# espurna-h.net
KiCad netlist of a schematic drawn in EAGLE
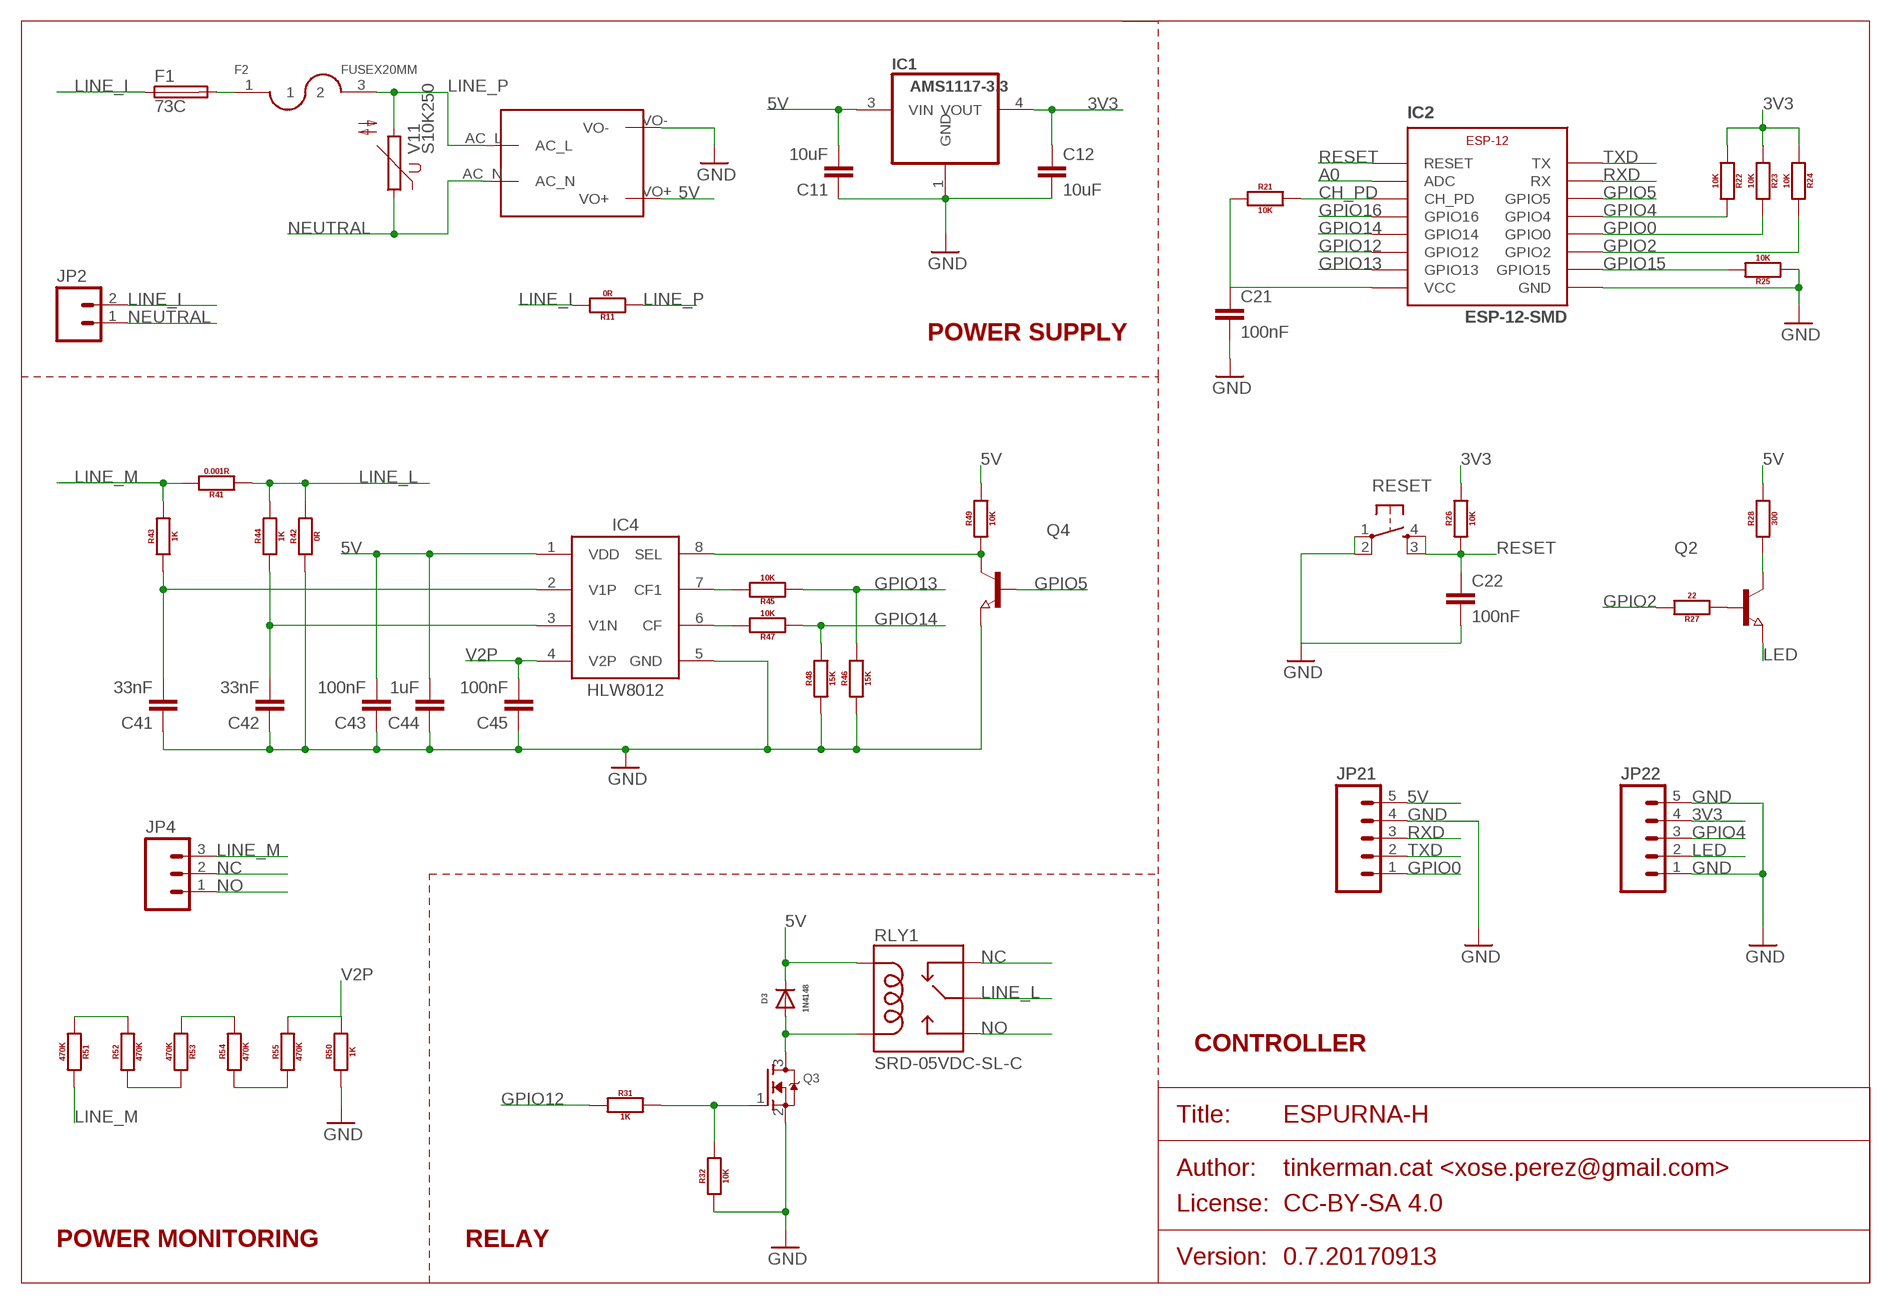
[diagram p0: schematic, sheet 1]

(export (version "E")
  (design (tool "Eeschema 10.0.6"))
  (components
    (comp (ref "C11")
      (value "10uF")
      (footprint "eagle-import:0805")
      (libsource (lib "eagle-import") (part "C-EU0805"))
    )
    (comp (ref "C12")
      (value "10uF")
      (footprint "eagle-import:0805")
      (libsource (lib "eagle-import") (part "C-EU0805"))
    )
    (comp (ref "C21")
      (value "100nF")
      (footprint "eagle-import:0805")
      (libsource (lib "eagle-import") (part "C-EU0805"))
    )
    (comp (ref "C22")
      (value "100nF")
      (footprint "eagle-import:0805")
      (libsource (lib "eagle-import") (part "C-EU0805"))
    )
    (comp (ref "C41")
      (value "33nF")
      (footprint "eagle-import:0805")
      (libsource (lib "eagle-import") (part "C-EU0805"))
    )
    (comp (ref "C42")
      (value "33nF")
      (footprint "eagle-import:0805")
      (libsource (lib "eagle-import") (part "C-EU0805"))
    )
    (comp (ref "C43")
      (value "100nF")
      (footprint "eagle-import:0805")
      (libsource (lib "eagle-import") (part "C-EU0805"))
    )
    (comp (ref "C44")
      (value "1uF")
      (footprint "eagle-import:0805")
      (libsource (lib "eagle-import") (part "C-EU0805"))
    )
    (comp (ref "C45")
      (value "100nF")
      (footprint "eagle-import:0805")
      (libsource (lib "eagle-import") (part "C-EU0805"))
    )
    (comp (ref "D3")
      (value "1N4148")
      (footprint "eagle-import:SOD80")
      (libsource (lib "eagle-import") (part "DIODE"))
    )
    (comp (ref "F1")
      (value "73C")
      (footprint "eagle-import:PICOFUSE")
      (libsource (lib "eagle-import") (part "PICOFUSE"))
    )
    (comp (ref "F2")
      (value "FUSEX20MM")
      (footprint "eagle-import:FUSE_5MM")
      (libsource (lib "eagle-import") (part "FUSEX20MM"))
    )
    (comp (ref "IC1")
      (value "AMS1117-3.3")
      (footprint "eagle-import:SOT223")
      (libsource (lib "eagle-import") (part "REG1117SOT223-2"))
    )
    (comp (ref "IC2")
      (value "ESP-12-SMD")
      (footprint "eagle-import:ESP-12-SMD")
      (libsource (lib "eagle-import") (part "ESP-12-SMD"))
    )
    (comp (ref "IC4")
      (value "HLW8012")
      (footprint "eagle-import:SOP8")
      (libsource (lib "eagle-import") (part "HLW8012"))
    )
    (comp (ref "JP2")
      (value "M02200MIL")
      (footprint "eagle-import:SCREWTERMINAL-200MIL-2")
      (libsource (lib "eagle-import") (part "M02200MIL"))
    )
    (comp (ref "JP4")
      (value "M03200MIL")
      (footprint "eagle-import:SCREWTERMINAL-200MIL-3")
      (libsource (lib "eagle-import") (part "M03200MIL"))
    )
    (comp (ref "JP21")
      (value "M05PTH")
      (footprint "eagle-import:1X05")
      (libsource (lib "eagle-import") (part "M05PTH"))
    )
    (comp (ref "JP22")
      (value "M05PTH")
      (footprint "eagle-import:1X05")
      (libsource (lib "eagle-import") (part "M05PTH"))
    )
    (comp (ref "Q2")
      (value "NPN-TRANSISTOR_SOT23")
      (footprint "eagle-import:SOT23")
      (libsource (lib "eagle-import") (part "NPN-TRANSISTOR_SOT23"))
    )
    (comp (ref "Q3")
      (value "MOSFET-NREFLOW")
      (footprint "eagle-import:SOT23")
      (libsource (lib "eagle-import") (part "MOSFET-NREFLOW"))
    )
    (comp (ref "Q4")
      (value "NPN-TRANSISTOR_SOT23")
      (footprint "eagle-import:SOT23")
      (libsource (lib "eagle-import") (part "NPN-TRANSISTOR_SOT23"))
    )
    (comp (ref "R11")
      (value "0R")
      (footprint "eagle-import:1206")
      (libsource (lib "eagle-import") (part "RESISTOR1206"))
    )
    (comp (ref "R21")
      (value "10K")
      (footprint "eagle-import:0805")
      (libsource (lib "eagle-import") (part "RESISTOR0805"))
    )
    (comp (ref "R22")
      (value "10K")
      (footprint "eagle-import:0805")
      (libsource (lib "eagle-import") (part "RESISTOR0805"))
    )
    (comp (ref "R23")
      (value "10K")
      (footprint "eagle-import:0805")
      (libsource (lib "eagle-import") (part "RESISTOR0805"))
    )
    (comp (ref "R24")
      (value "10K")
      (footprint "eagle-import:0805")
      (libsource (lib "eagle-import") (part "RESISTOR0805"))
    )
    (comp (ref "R25")
      (value "10K")
      (footprint "eagle-import:0805")
      (libsource (lib "eagle-import") (part "RESISTOR0805"))
    )
    (comp (ref "R26")
      (value "10K")
      (footprint "eagle-import:0805")
      (libsource (lib "eagle-import") (part "RESISTOR0805"))
    )
    (comp (ref "R27")
      (value "22")
      (footprint "eagle-import:0805")
      (libsource (lib "eagle-import") (part "RESISTOR0805"))
    )
    (comp (ref "R28")
      (value "300")
      (footprint "eagle-import:0805")
      (libsource (lib "eagle-import") (part "RESISTOR0805"))
    )
    (comp (ref "R31")
      (value "1K")
      (footprint "eagle-import:0805")
      (libsource (lib "eagle-import") (part "RESISTOR0805"))
    )
    (comp (ref "R32")
      (value "10K")
      (footprint "eagle-import:0805")
      (libsource (lib "eagle-import") (part "RESISTOR0805"))
    )
    (comp (ref "R41")
      (value "0.001R")
      (footprint "eagle-import:2512")
      (libsource (lib "eagle-import") (part "RESISTOR2512"))
    )
    (comp (ref "R42")
      (value "0R")
      (footprint "eagle-import:1206")
      (libsource (lib "eagle-import") (part "RESISTOR1206"))
    )
    (comp (ref "R43")
      (value "1K")
      (footprint "eagle-import:0805")
      (libsource (lib "eagle-import") (part "RESISTOR0805"))
    )
    (comp (ref "R44")
      (value "1K")
      (footprint "eagle-import:0805")
      (libsource (lib "eagle-import") (part "RESISTOR0805"))
    )
    (comp (ref "R45")
      (value "10K")
      (footprint "eagle-import:0805")
      (libsource (lib "eagle-import") (part "RESISTOR0805"))
    )
    (comp (ref "R46")
      (value "15K")
      (footprint "eagle-import:0805")
      (libsource (lib "eagle-import") (part "RESISTOR0805"))
    )
    (comp (ref "R47")
      (value "10K")
      (footprint "eagle-import:0805")
      (libsource (lib "eagle-import") (part "RESISTOR0805"))
    )
    (comp (ref "R48")
      (value "15K")
      (footprint "eagle-import:0805")
      (libsource (lib "eagle-import") (part "RESISTOR0805"))
    )
    (comp (ref "R49")
      (value "10K")
      (footprint "eagle-import:0805")
      (libsource (lib "eagle-import") (part "RESISTOR0805"))
    )
    (comp (ref "R50")
      (value "1K")
      (footprint "eagle-import:0805")
      (libsource (lib "eagle-import") (part "RESISTOR0805"))
    )
    (comp (ref "R51")
      (value "470K")
      (footprint "eagle-import:0805")
      (libsource (lib "eagle-import") (part "RESISTOR0805"))
    )
    (comp (ref "R52")
      (value "470K")
      (footprint "eagle-import:0805")
      (libsource (lib "eagle-import") (part "RESISTOR0805"))
    )
    (comp (ref "R53")
      (value "470K")
      (footprint "eagle-import:0805")
      (libsource (lib "eagle-import") (part "RESISTOR0805"))
    )
    (comp (ref "R54")
      (value "470K")
      (footprint "eagle-import:0805")
      (libsource (lib "eagle-import") (part "RESISTOR0805"))
    )
    (comp (ref "R55")
      (value "470K")
      (footprint "eagle-import:0805")
      (libsource (lib "eagle-import") (part "RESISTOR0805"))
    )
    (comp (ref "RESET")
      (value "TACTILE_BUTTON_SMD")
      (footprint "eagle-import:TACTILE-BUTTON-SMD")
      (libsource (lib "eagle-import") (part "TACTILE_BUTTON_SMD"))
    )
    (comp (ref "RLY1")
      (value "SRD-05VDC-SL-C")
      (footprint "eagle-import:SRD-5VDC-SL-C")
      (libsource (lib "eagle-import") (part "RELAYSONGLE"))
    )
    (comp (ref "U$1")
      (value "MAINS_CONVERTERS")
      (footprint "eagle-import:HLK-PM01")
      (libsource (lib "eagle-import") (part "MAINS_CONVERTERS"))
    )
    (comp (ref "V11")
      (value "S10K250")
      (footprint "eagle-import:S10K250")
      (libsource (lib "eagle-import") (part "S10K250"))
    )
  )
  (nets
    (net (code "1") (name "/3V3") (class "Default")
      (node (ref "C12") (pin "1") (pinfunction "1_1") (pintype "passive"))
      (node (ref "C21") (pin "1") (pinfunction "1_1") (pintype "passive"))
      (node (ref "IC1") (pin "4") (pinfunction "VOUT_4") (pintype "output"))
      (node (ref "IC2") (pin "VCC") (pinfunction "VCC_VCC") (pintype "bidirectional"))
      (node (ref "JP22") (pin "4") (pinfunction "4_4") (pintype "passive"))
      (node (ref "R21") (pin "1") (pinfunction "1_1") (pintype "passive"))
      (node (ref "R22") (pin "1") (pinfunction "1_1") (pintype "passive"))
      (node (ref "R23") (pin "1") (pinfunction "1_1") (pintype "passive"))
      (node (ref "R24") (pin "1") (pinfunction "1_1") (pintype "passive"))
      (node (ref "R26") (pin "2") (pinfunction "2_2") (pintype "passive"))
    )
    (net (code "2") (name "/5V") (class "Default")
      (node (ref "C11") (pin "2") (pinfunction "2_2") (pintype "passive"))
      (node (ref "C43") (pin "2") (pinfunction "2_2") (pintype "passive"))
      (node (ref "C44") (pin "2") (pinfunction "2_2") (pintype "passive"))
      (node (ref "D3") (pin "2") (pinfunction "C_2") (pintype "passive"))
      (node (ref "IC1") (pin "3") (pinfunction "VIN_3") (pintype "input"))
      (node (ref "IC4") (pin "1") (pinfunction "VDD_1") (pintype "power_in"))
      (node (ref "JP21") (pin "5") (pinfunction "5_5") (pintype "passive"))
      (node (ref "R28") (pin "2") (pinfunction "2_2") (pintype "passive"))
      (node (ref "R49") (pin "2") (pinfunction "2_2") (pintype "passive"))
      (node (ref "RLY1") (pin "COIL1") (pinfunction "COIL1_COIL1") (pintype "bidirectional"))
      (node (ref "U$1") (pin "VO+") (pinfunction "VO+_VO+") (pintype "output"))
    )
    (net (code "3") (name "/A0") (class "Default")
      (node (ref "IC2") (pin "ADC") (pinfunction "ADC_ADC") (pintype "bidirectional"))
    )
    (net (code "4") (name "/CH_PD") (class "Default")
      (node (ref "IC2") (pin "CH_PD") (pinfunction "CH_PD_CH_PD") (pintype "bidirectional"))
      (node (ref "R21") (pin "2") (pinfunction "2_2") (pintype "passive"))
    )
    (net (code "5") (name "/GPIO0") (class "Default")
      (node (ref "IC2") (pin "GPIO0") (pinfunction "GPIO0_GPIO0") (pintype "bidirectional"))
      (node (ref "JP21") (pin "1") (pinfunction "1_1") (pintype "passive"))
      (node (ref "R23") (pin "2") (pinfunction "2_2") (pintype "passive"))
    )
    (net (code "6") (name "/GPIO2") (class "Default")
      (node (ref "IC2") (pin "GPIO2") (pinfunction "GPIO2_GPIO2") (pintype "bidirectional"))
      (node (ref "R24") (pin "2") (pinfunction "2_2") (pintype "passive"))
      (node (ref "R27") (pin "2") (pinfunction "2_2") (pintype "passive"))
    )
    (net (code "7") (name "/GPIO4") (class "Default")
      (node (ref "IC2") (pin "GPIO4") (pinfunction "GPIO4_GPIO4") (pintype "bidirectional"))
      (node (ref "JP22") (pin "3") (pinfunction "3_3") (pintype "passive"))
      (node (ref "R22") (pin "2") (pinfunction "2_2") (pintype "passive"))
    )
    (net (code "8") (name "/GPIO5") (class "Default")
      (node (ref "IC2") (pin "GPIO5") (pinfunction "GPIO5_GPIO5") (pintype "bidirectional"))
      (node (ref "Q4") (pin "1") (pinfunction "B_1") (pintype "passive"))
    )
    (net (code "9") (name "/GPIO12") (class "Default")
      (node (ref "IC2") (pin "GPIO12") (pinfunction "GPIO12_GPIO12") (pintype "bidirectional"))
      (node (ref "R31") (pin "1") (pinfunction "1_1") (pintype "passive"))
    )
    (net (code "10") (name "/GPIO13") (class "Default")
      (node (ref "IC2") (pin "GPIO13") (pinfunction "GPIO13_GPIO13") (pintype "bidirectional"))
      (node (ref "R45") (pin "1") (pinfunction "1_1") (pintype "passive"))
      (node (ref "R46") (pin "2") (pinfunction "2_2") (pintype "passive"))
    )
    (net (code "11") (name "/GPIO14") (class "Default")
      (node (ref "IC2") (pin "GPIO14") (pinfunction "GPIO14_GPIO14") (pintype "bidirectional"))
      (node (ref "R47") (pin "1") (pinfunction "1_1") (pintype "passive"))
      (node (ref "R48") (pin "2") (pinfunction "2_2") (pintype "passive"))
    )
    (net (code "12") (name "/GPIO15") (class "Default")
      (node (ref "IC2") (pin "GPIO15") (pinfunction "GPIO15_GPIO15") (pintype "bidirectional"))
      (node (ref "R25") (pin "2") (pinfunction "2_2") (pintype "passive"))
    )
    (net (code "13") (name "/GPIO16") (class "Default")
      (node (ref "IC2") (pin "GPIO16") (pinfunction "GPIO16_GPIO16") (pintype "bidirectional"))
    )
    (net (code "14") (name "/LED") (class "Default")
      (node (ref "JP22") (pin "2") (pinfunction "2_2") (pintype "passive"))
      (node (ref "Q2") (pin "2") (pinfunction "E_2") (pintype "passive"))
    )
    (net (code "15") (name "/LINE_I") (class "Default")
      (node (ref "F1") (pin "1") (pinfunction "1_1") (pintype "passive"))
      (node (ref "JP2") (pin "2") (pinfunction "2_2") (pintype "passive"))
      (node (ref "R11") (pin "2") (pinfunction "2_2") (pintype "passive"))
    )
    (net (code "16") (name "/LINE_L") (class "Default")
      (node (ref "R41") (pin "1") (pinfunction "1_1") (pintype "passive"))
      (node (ref "R42") (pin "2") (pinfunction "2_2") (pintype "passive"))
      (node (ref "R44") (pin "2") (pinfunction "2_2") (pintype "passive"))
      (node (ref "RLY1") (pin "COMMON") (pinfunction "MAIN_COMMON") (pintype "bidirectional"))
    )
    (net (code "17") (name "/LINE_M") (class "Default")
      (node (ref "JP4") (pin "3") (pinfunction "3_3") (pintype "passive"))
      (node (ref "R41") (pin "2") (pinfunction "2_2") (pintype "passive"))
      (node (ref "R43") (pin "2") (pinfunction "2_2") (pintype "passive"))
      (node (ref "R51") (pin "2") (pinfunction "2_2") (pintype "passive"))
    )
    (net (code "18") (name "/LINE_P") (class "Default")
      (node (ref "F2") (pin "3") (pinfunction "2_3") (pintype "bidirectional"))
      (node (ref "R11") (pin "1") (pinfunction "1_1") (pintype "passive"))
      (node (ref "U$1") (pin "AC_L") (pinfunction "AC_L_AC_L") (pintype "input"))
      (node (ref "V11") (pin "2") (pinfunction "2_2") (pintype "passive"))
    )
    (net (code "19") (name "/NC") (class "Default")
      (node (ref "JP4") (pin "2") (pinfunction "2_2") (pintype "passive"))
      (node (ref "RLY1") (pin "CLOSED") (pinfunction "NC_CLOSED") (pintype "bidirectional"))
    )
    (net (code "20") (name "/NEUTRAL") (class "Default")
      (node (ref "JP2") (pin "1") (pinfunction "1_1") (pintype "passive"))
      (node (ref "U$1") (pin "AC_N") (pinfunction "AC_N_AC_N") (pintype "input"))
      (node (ref "V11") (pin "1") (pinfunction "1_1") (pintype "passive"))
    )
    (net (code "21") (name "/NO") (class "Default")
      (node (ref "JP4") (pin "1") (pinfunction "1_1") (pintype "passive"))
      (node (ref "RLY1") (pin "OPEN") (pinfunction "NO_OPEN") (pintype "bidirectional"))
    )
    (net (code "22") (name "/RESET") (class "Default")
      (node (ref "C22") (pin "1") (pinfunction "1_1") (pintype "passive"))
      (node (ref "IC2") (pin "RESET") (pinfunction "RESET_RESET") (pintype "bidirectional"))
      (node (ref "R26") (pin "1") (pinfunction "1_1") (pintype "passive"))
      (node (ref "RESET") (pin "3") (pinfunction "SWB2_3") (pintype "passive"))
      (node (ref "RESET") (pin "4") (pinfunction "SWA2_4") (pintype "passive"))
    )
    (net (code "23") (name "/RXD") (class "Default")
      (node (ref "IC2") (pin "RX") (pinfunction "RX_RX") (pintype "bidirectional"))
      (node (ref "JP21") (pin "3") (pinfunction "3_3") (pintype "passive"))
    )
    (net (code "24") (name "/TXD") (class "Default")
      (node (ref "IC2") (pin "TX") (pinfunction "TX_TX") (pintype "bidirectional"))
      (node (ref "JP21") (pin "2") (pinfunction "2_2") (pintype "passive"))
    )
    (net (code "25") (name "/V2P") (class "Default")
      (node (ref "C45") (pin "2") (pinfunction "2_2") (pintype "passive"))
      (node (ref "IC4") (pin "4") (pinfunction "V2P_4") (pintype "input"))
      (node (ref "R50") (pin "2") (pinfunction "2_2") (pintype "passive"))
      (node (ref "R55") (pin "2") (pinfunction "2_2") (pintype "passive"))
    )
    (net (code "26") (name "GND") (class "Default")
      (node (ref "C11") (pin "1") (pinfunction "1_1") (pintype "passive"))
      (node (ref "C12") (pin "2") (pinfunction "2_2") (pintype "passive"))
      (node (ref "C21") (pin "2") (pinfunction "2_2") (pintype "passive"))
      (node (ref "C22") (pin "2") (pinfunction "2_2") (pintype "passive"))
      (node (ref "C41") (pin "1") (pinfunction "1_1") (pintype "passive"))
      (node (ref "C42") (pin "1") (pinfunction "1_1") (pintype "passive"))
      (node (ref "C43") (pin "1") (pinfunction "1_1") (pintype "passive"))
      (node (ref "C44") (pin "1") (pinfunction "1_1") (pintype "passive"))
      (node (ref "C45") (pin "1") (pinfunction "1_1") (pintype "passive"))
      (node (ref "IC1") (pin "1") (pinfunction "GND_1") (pintype "power_in"))
      (node (ref "IC2") (pin "GND") (pinfunction "GND_GND") (pintype "bidirectional"))
      (node (ref "IC4") (pin "5") (pinfunction "GND_5") (pintype "power_in"))
      (node (ref "JP21") (pin "4") (pinfunction "4_4") (pintype "passive"))
      (node (ref "JP22") (pin "1") (pinfunction "1_1") (pintype "passive"))
      (node (ref "JP22") (pin "5") (pinfunction "5_5") (pintype "passive"))
      (node (ref "Q3") (pin "2") (pinfunction "S_2") (pintype "bidirectional"))
      (node (ref "Q4") (pin "2") (pinfunction "E_2") (pintype "passive"))
      (node (ref "R25") (pin "1") (pinfunction "1_1") (pintype "passive"))
      (node (ref "R32") (pin "1") (pinfunction "1_1") (pintype "passive"))
      (node (ref "R42") (pin "1") (pinfunction "1_1") (pintype "passive"))
      (node (ref "R46") (pin "1") (pinfunction "1_1") (pintype "passive"))
      (node (ref "R48") (pin "1") (pinfunction "1_1") (pintype "passive"))
      (node (ref "R50") (pin "1") (pinfunction "1_1") (pintype "passive"))
      (node (ref "RESET") (pin "1") (pinfunction "SWA1_1") (pintype "passive"))
      (node (ref "RESET") (pin "2") (pinfunction "SWB1_2") (pintype "passive"))
      (node (ref "U$1") (pin "VO-") (pinfunction "VO-_VO-") (pintype "output"))
    )
    (net (code "27") (name "Net-(D3-A)") (class "Default")
      (node (ref "D3") (pin "1") (pinfunction "A_1") (pintype "passive"))
      (node (ref "Q3") (pin "3") (pinfunction "D_3") (pintype "bidirectional"))
      (node (ref "RLY1") (pin "COIL2") (pinfunction "COIL2_COIL2") (pintype "bidirectional"))
    )
    (net (code "28") (name "Net-(F1-Pad2)") (class "Default")
      (node (ref "F1") (pin "2") (pinfunction "2_2") (pintype "passive"))
      (node (ref "F2") (pin "1") (pinfunction "1_1") (pintype "bidirectional"))
    )
    (net (code "29") (name "Net-(IC4-CF)") (class "Default")
      (node (ref "IC4") (pin "6") (pinfunction "CF_6") (pintype "output"))
      (node (ref "R47") (pin "2") (pinfunction "2_2") (pintype "passive"))
    )
    (net (code "30") (name "Net-(IC4-CF1)") (class "Default")
      (node (ref "IC4") (pin "7") (pinfunction "CF1_7") (pintype "output"))
      (node (ref "R45") (pin "2") (pinfunction "2_2") (pintype "passive"))
    )
    (net (code "31") (name "Net-(IC4-SEL)") (class "Default")
      (node (ref "IC4") (pin "8") (pinfunction "SEL_8") (pintype "input"))
      (node (ref "Q4") (pin "3") (pinfunction "C_3") (pintype "passive"))
      (node (ref "R49") (pin "1") (pinfunction "1_1") (pintype "passive"))
    )
    (net (code "32") (name "Net-(IC4-V1N)") (class "Default")
      (node (ref "C42") (pin "2") (pinfunction "2_2") (pintype "passive"))
      (node (ref "IC4") (pin "3") (pinfunction "V1N_3") (pintype "input"))
      (node (ref "R44") (pin "1") (pinfunction "1_1") (pintype "passive"))
    )
    (net (code "33") (name "Net-(IC4-V1P)") (class "Default")
      (node (ref "C41") (pin "2") (pinfunction "2_2") (pintype "passive"))
      (node (ref "IC4") (pin "2") (pinfunction "V1P_2") (pintype "input"))
      (node (ref "R43") (pin "1") (pinfunction "1_1") (pintype "passive"))
    )
    (net (code "34") (name "Net-(Q2-B)") (class "Default")
      (node (ref "Q2") (pin "1") (pinfunction "B_1") (pintype "passive"))
      (node (ref "R27") (pin "1") (pinfunction "1_1") (pintype "passive"))
    )
    (net (code "35") (name "Net-(Q2-C)") (class "Default")
      (node (ref "Q2") (pin "3") (pinfunction "C_3") (pintype "passive"))
      (node (ref "R28") (pin "1") (pinfunction "1_1") (pintype "passive"))
    )
    (net (code "36") (name "Net-(Q3-G)") (class "Default")
      (node (ref "Q3") (pin "1") (pinfunction "G_1") (pintype "bidirectional"))
      (node (ref "R31") (pin "2") (pinfunction "2_2") (pintype "passive"))
      (node (ref "R32") (pin "2") (pinfunction "2_2") (pintype "passive"))
    )
    (net (code "37") (name "Net-(R51-Pad1)") (class "Default")
      (node (ref "R51") (pin "1") (pinfunction "1_1") (pintype "passive"))
      (node (ref "R52") (pin "2") (pinfunction "2_2") (pintype "passive"))
    )
    (net (code "38") (name "Net-(R52-Pad1)") (class "Default")
      (node (ref "R52") (pin "1") (pinfunction "1_1") (pintype "passive"))
      (node (ref "R53") (pin "2") (pinfunction "2_2") (pintype "passive"))
    )
    (net (code "39") (name "Net-(R53-Pad1)") (class "Default")
      (node (ref "R53") (pin "1") (pinfunction "1_1") (pintype "passive"))
      (node (ref "R54") (pin "2") (pinfunction "2_2") (pintype "passive"))
    )
    (net (code "40") (name "Net-(R54-Pad1)") (class "Default")
      (node (ref "R54") (pin "1") (pinfunction "1_1") (pintype "passive"))
      (node (ref "R55") (pin "1") (pinfunction "1_1") (pintype "passive"))
    )
  )
)
